# StationModule.net
KiCad netlist of a schematic drawn in EAGLE
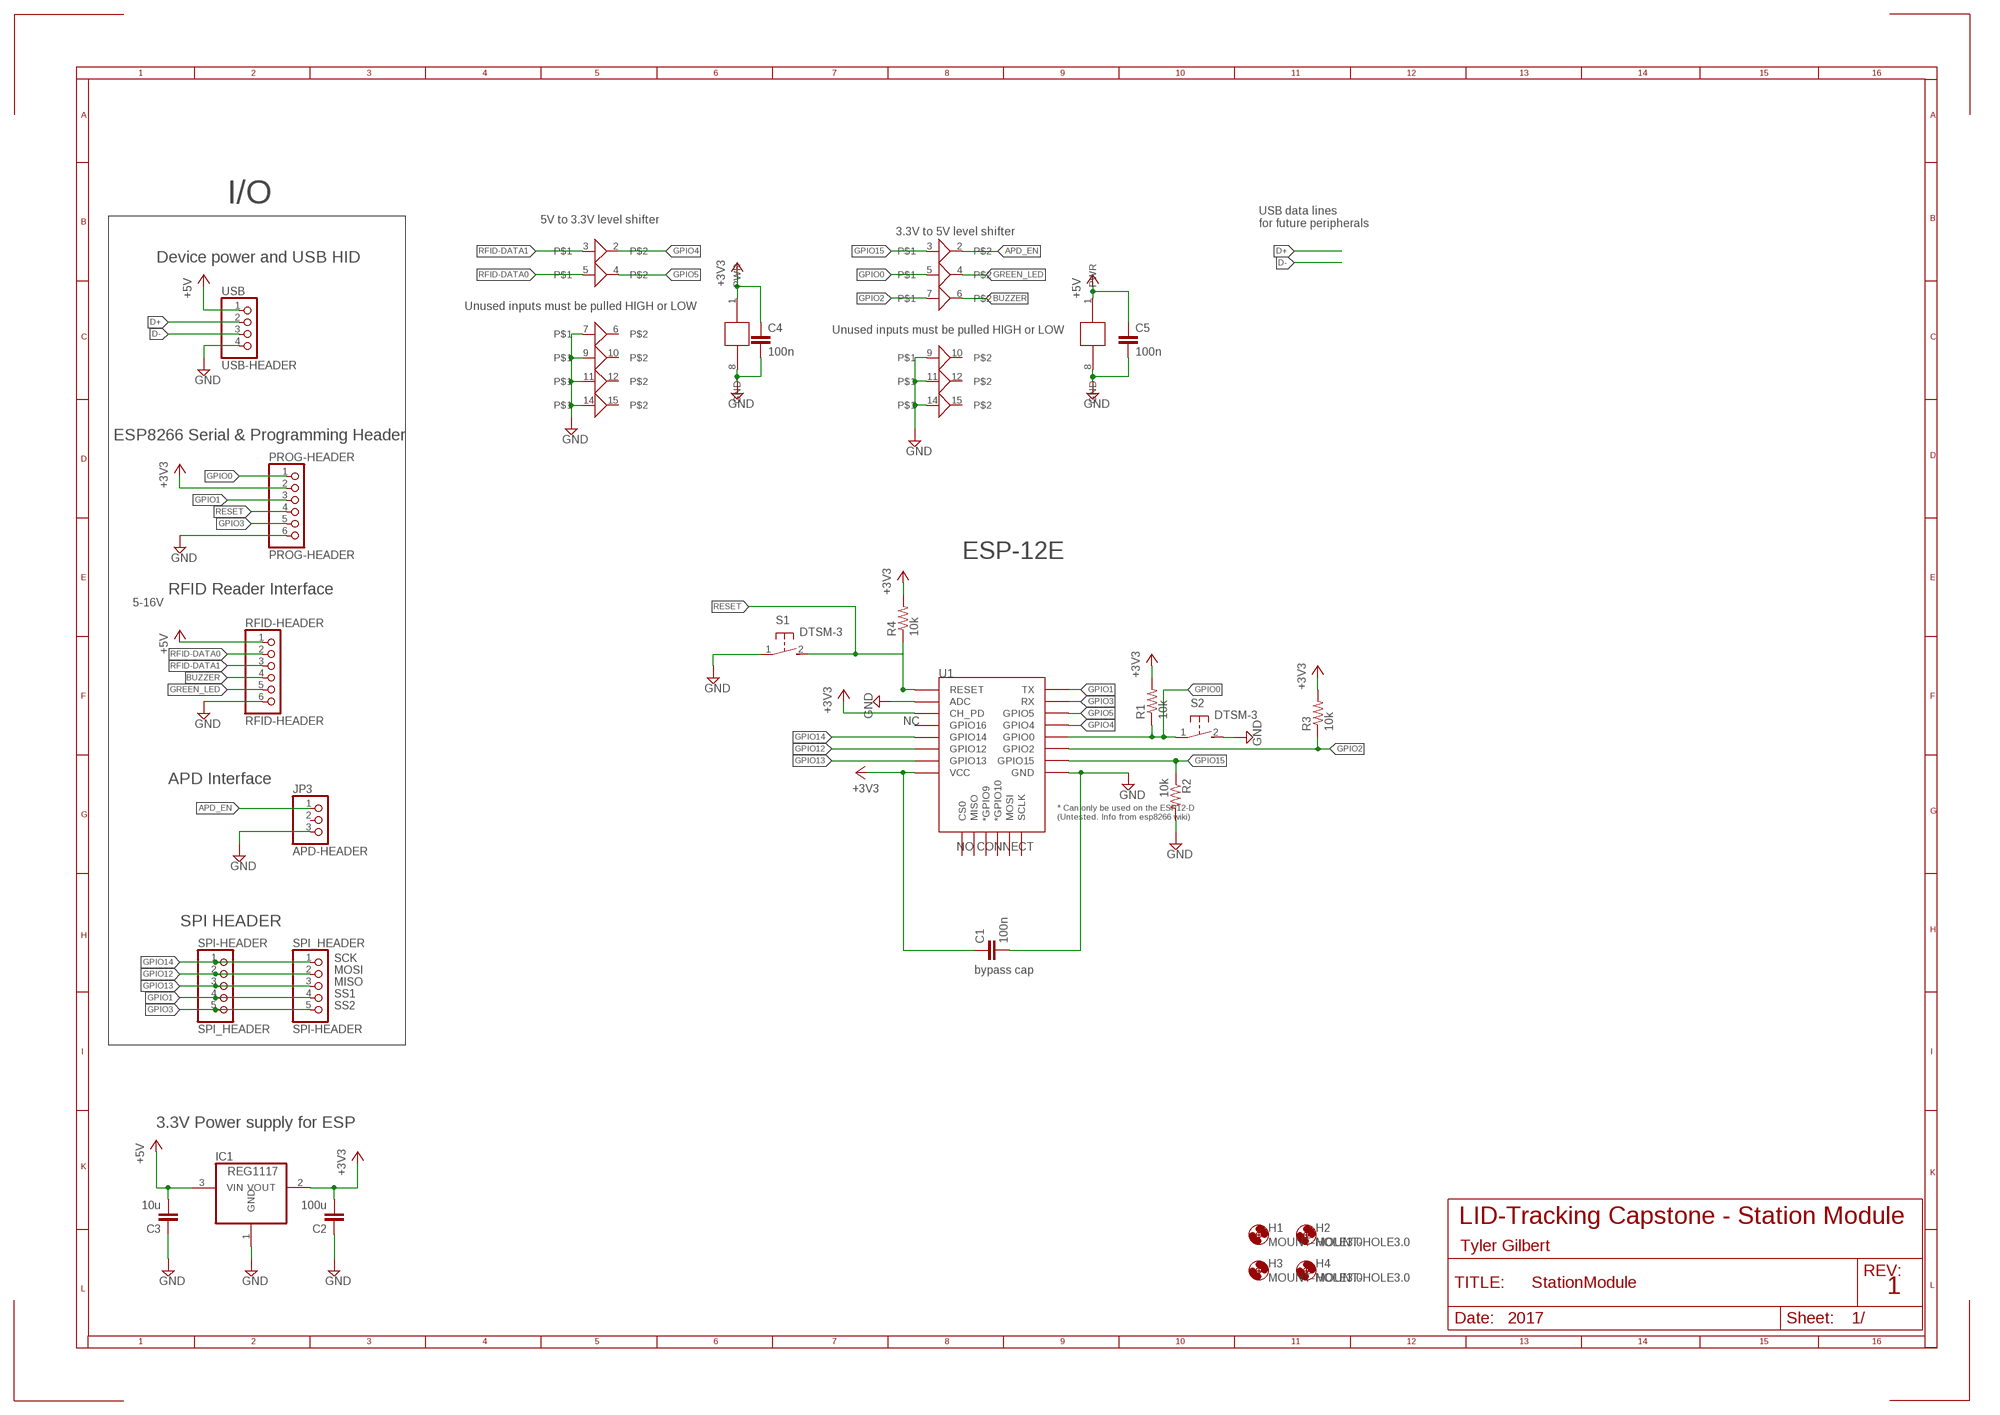
[diagram p0: schematic, sheet 1]

(export (version "E")
  (design (tool "Eeschema 10.0.6"))
  (components
    (comp (ref "C1")
      (value "100n")
      (footprint "eagle-import:C0805K")
      (libsource (lib "eagle-import") (part "C-EUC0805K"))
    )
    (comp (ref "C2")
      (value "100u")
      (footprint "eagle-import:C0805K")
      (libsource (lib "eagle-import") (part "C-EUC0805K"))
    )
    (comp (ref "C3")
      (value "10u")
      (footprint "eagle-import:C0805K")
      (libsource (lib "eagle-import") (part "C-EUC0805K"))
    )
    (comp (ref "C4")
      (value "100n")
      (footprint "eagle-import:C0805K")
      (libsource (lib "eagle-import") (part "C-EUC0805K"))
    )
    (comp (ref "C5")
      (value "100n")
      (footprint "eagle-import:C0805K")
      (libsource (lib "eagle-import") (part "C-EUC0805K"))
    )
    (comp (ref "H1")
      (value "MOUNT-HOLE3.0")
      (footprint "eagle-import:3,0")
      (libsource (lib "eagle-import") (part "MOUNT-HOLE3.0"))
    )
    (comp (ref "H2")
      (value "MOUNT-HOLE3.0")
      (footprint "eagle-import:3,0")
      (libsource (lib "eagle-import") (part "MOUNT-HOLE3.0"))
    )
    (comp (ref "H3")
      (value "MOUNT-HOLE3.0")
      (footprint "eagle-import:3,0")
      (libsource (lib "eagle-import") (part "MOUNT-HOLE3.0"))
    )
    (comp (ref "H4")
      (value "MOUNT-HOLE3.0")
      (footprint "eagle-import:3,0")
      (libsource (lib "eagle-import") (part "MOUNT-HOLE3.0"))
    )
    (comp (ref "IC1")
      (value "REG1117")
      (footprint "eagle-import:SOT223")
      (libsource (lib "eagle-import") (part "REG1117"))
    )
    (comp (ref "JP3")
      (value "APD-HEADER")
      (footprint "eagle-import:1X03")
      (libsource (lib "eagle-import") (part "PINHD-1X3"))
    )
    (comp (ref "PROG-HEADER")
      (value "PROG-HEADER")
      (footprint "eagle-import:1X06")
      (libsource (lib "eagle-import") (part "PINHD-1X6"))
    )
    (comp (ref "R1")
      (value "10k")
      (footprint "eagle-import:R0805")
      (libsource (lib "eagle-import") (part "R-US_R0805"))
    )
    (comp (ref "R2")
      (value "10k")
      (footprint "eagle-import:R0805")
      (libsource (lib "eagle-import") (part "R-US_R0805"))
    )
    (comp (ref "R3")
      (value "10k")
      (footprint "eagle-import:R0805")
      (libsource (lib "eagle-import") (part "R-US_R0805"))
    )
    (comp (ref "R4")
      (value "10k")
      (footprint "eagle-import:R0805")
      (libsource (lib "eagle-import") (part "R-US_R0805"))
    )
    (comp (ref "RFID-HEADER")
      (value "RFID-HEADER")
      (footprint "eagle-import:1X06")
      (libsource (lib "eagle-import") (part "PINHD-1X6"))
    )
    (comp (ref "S1")
      (value "DTSM-3")
      (footprint "eagle-import:DTSM-3")
      (libsource (lib "eagle-import") (part "DTSM-3"))
    )
    (comp (ref "S2")
      (value "DTSM-3")
      (footprint "eagle-import:DTSM-3")
      (libsource (lib "eagle-import") (part "DTSM-3"))
    )
    (comp (ref "SPI-HEADER")
      (value "SPI_HEADER")
      (footprint "eagle-import:1X05")
      (libsource (lib "eagle-import") (part "PINHD-1X5"))
    )
    (comp (ref "SPI_HEADER")
      (value "SPI-HEADER")
      (footprint "eagle-import:1X05")
      (libsource (lib "eagle-import") (part "PINHD-1X5"))
    )
    (comp (ref "U$1")
      (value "4050B")
      (footprint "eagle-import:SOIC16N")
      (libsource (lib "eagle-import") (part "4050B"))
    )
    (comp (ref "U$2")
      (value "4050B")
      (footprint "eagle-import:SOIC16N")
      (libsource (lib "eagle-import") (part "4050B"))
    )
    (comp (ref "U1")
      (value "ESP12ESMD")
      (footprint "eagle-import:ESP12E-SMD")
      (libsource (lib "eagle-import") (part "ESP12ESMD"))
    )
    (comp (ref "USB")
      (value "USB-HEADER")
      (footprint "eagle-import:1X04")
      (libsource (lib "eagle-import") (part "PINHD-1X4"))
    )
  )
  (nets
    (net (code "1") (name "+3V3") (class "Default")
      (node (ref "C1") (pin "1") (pinfunction "1_1") (pintype "passive"))
      (node (ref "C2") (pin "2") (pinfunction "2_2") (pintype "passive"))
      (node (ref "C4") (pin "1") (pinfunction "1_1") (pintype "passive"))
      (node (ref "IC1") (pin "2") (pinfunction "VOUT_2") (pintype "output"))
      (node (ref "PROG-HEADER") (pin "2") (pinfunction "2_2") (pintype "passive"))
      (node (ref "R1") (pin "2") (pinfunction "2_2") (pintype "passive"))
      (node (ref "R3") (pin "2") (pinfunction "2_2") (pintype "passive"))
      (node (ref "R4") (pin "2") (pinfunction "2_2") (pintype "passive"))
      (node (ref "U$1") (pin "1") (pinfunction "PWR_1") (pintype "power_in"))
      (node (ref "U1") (pin "CH_PD") (pinfunction "CH_PD_CH_PD") (pintype "bidirectional"))
      (node (ref "U1") (pin "VCC") (pinfunction "VCC_VCC") (pintype "bidirectional"))
    )
    (net (code "2") (name "+5V") (class "Default")
      (node (ref "C3") (pin "2") (pinfunction "2_2") (pintype "passive"))
      (node (ref "C5") (pin "1") (pinfunction "1_1") (pintype "passive"))
      (node (ref "IC1") (pin "3") (pinfunction "VIN_3") (pintype "input"))
      (node (ref "RFID-HEADER") (pin "1") (pinfunction "1_1") (pintype "passive"))
      (node (ref "U$2") (pin "1") (pinfunction "PWR_1") (pintype "power_in"))
      (node (ref "USB") (pin "1") (pinfunction "1_1") (pintype "passive"))
    )
    (net (code "3") (name "APD_EN") (class "Default")
      (node (ref "JP3") (pin "1") (pinfunction "1_1") (pintype "passive"))
      (node (ref "U$2") (pin "2") (pinfunction "P$2_2") (pintype "bidirectional"))
    )
    (net (code "4") (name "BUZZER") (class "Default")
      (node (ref "RFID-HEADER") (pin "4") (pinfunction "4_4") (pintype "passive"))
      (node (ref "U$2") (pin "6") (pinfunction "P$2_6") (pintype "bidirectional"))
    )
    (net (code "5") (name "D+") (class "Default")
      (node (ref "USB") (pin "2") (pinfunction "2_2") (pintype "passive"))
    )
    (net (code "6") (name "D-") (class "Default")
      (node (ref "USB") (pin "3") (pinfunction "3_3") (pintype "passive"))
    )
    (net (code "7") (name "GND") (class "Default")
      (node (ref "C1") (pin "2") (pinfunction "2_2") (pintype "passive"))
      (node (ref "C2") (pin "1") (pinfunction "1_1") (pintype "passive"))
      (node (ref "C3") (pin "1") (pinfunction "1_1") (pintype "passive"))
      (node (ref "C4") (pin "2") (pinfunction "2_2") (pintype "passive"))
      (node (ref "C5") (pin "2") (pinfunction "2_2") (pintype "passive"))
      (node (ref "IC1") (pin "1") (pinfunction "GND_1") (pintype "power_in"))
      (node (ref "JP3") (pin "3") (pinfunction "3_3") (pintype "passive"))
      (node (ref "PROG-HEADER") (pin "6") (pinfunction "6_6") (pintype "passive"))
      (node (ref "R2") (pin "2") (pinfunction "2_2") (pintype "passive"))
      (node (ref "RFID-HEADER") (pin "6") (pinfunction "6_6") (pintype "passive"))
      (node (ref "S1") (pin "1") (pinfunction "1_1") (pintype "passive"))
      (node (ref "S2") (pin "2") (pinfunction "2_2") (pintype "passive"))
      (node (ref "U$1") (pin "11") (pinfunction "P$1_11") (pintype "bidirectional"))
      (node (ref "U$1") (pin "14") (pinfunction "P$1_14") (pintype "bidirectional"))
      (node (ref "U$1") (pin "7") (pinfunction "P$1_7") (pintype "bidirectional"))
      (node (ref "U$1") (pin "8") (pinfunction "GND_8") (pintype "power_in"))
      (node (ref "U$1") (pin "9") (pinfunction "P$1_9") (pintype "bidirectional"))
      (node (ref "U$2") (pin "11") (pinfunction "P$1_11") (pintype "bidirectional"))
      (node (ref "U$2") (pin "14") (pinfunction "P$1_14") (pintype "bidirectional"))
      (node (ref "U$2") (pin "8") (pinfunction "GND_8") (pintype "power_in"))
      (node (ref "U$2") (pin "9") (pinfunction "P$1_9") (pintype "bidirectional"))
      (node (ref "U1") (pin "ADC") (pinfunction "ADC_ADC") (pintype "bidirectional"))
      (node (ref "U1") (pin "GND") (pinfunction "GND_GND") (pintype "bidirectional"))
      (node (ref "USB") (pin "4") (pinfunction "4_4") (pintype "passive"))
    )
    (net (code "8") (name "GPIO0") (class "Default")
      (node (ref "PROG-HEADER") (pin "1") (pinfunction "1_1") (pintype "passive"))
      (node (ref "R1") (pin "1") (pinfunction "1_1") (pintype "passive"))
      (node (ref "S2") (pin "1") (pinfunction "1_1") (pintype "passive"))
      (node (ref "U$2") (pin "5") (pinfunction "P$1_5") (pintype "bidirectional"))
      (node (ref "U1") (pin "GPIO0") (pinfunction "GPIO0_GPIO0") (pintype "bidirectional"))
    )
    (net (code "9") (name "GPIO1") (class "Default")
      (node (ref "PROG-HEADER") (pin "3") (pinfunction "3_3") (pintype "passive"))
      (node (ref "SPI-HEADER") (pin "4") (pinfunction "4_4") (pintype "passive"))
      (node (ref "SPI_HEADER") (pin "4") (pinfunction "4_4") (pintype "passive"))
      (node (ref "U1") (pin "TXD0") (pinfunction "TX_TXD0") (pintype "bidirectional"))
    )
    (net (code "10") (name "GPIO2") (class "Default")
      (node (ref "R3") (pin "1") (pinfunction "1_1") (pintype "passive"))
      (node (ref "U$2") (pin "7") (pinfunction "P$1_7") (pintype "bidirectional"))
      (node (ref "U1") (pin "GPIO2") (pinfunction "GPIO2_GPIO2") (pintype "bidirectional"))
    )
    (net (code "11") (name "GPIO3") (class "Default")
      (node (ref "PROG-HEADER") (pin "5") (pinfunction "5_5") (pintype "passive"))
      (node (ref "SPI-HEADER") (pin "5") (pinfunction "5_5") (pintype "passive"))
      (node (ref "SPI_HEADER") (pin "5") (pinfunction "5_5") (pintype "passive"))
      (node (ref "U1") (pin "RXD0") (pinfunction "RX_RXD0") (pintype "bidirectional"))
    )
    (net (code "12") (name "GPIO4") (class "Default")
      (node (ref "U$1") (pin "2") (pinfunction "P$2_2") (pintype "bidirectional"))
      (node (ref "U1") (pin "GPIO4") (pinfunction "GPIO4_GPIO4") (pintype "bidirectional"))
    )
    (net (code "13") (name "GPIO5") (class "Default")
      (node (ref "U$1") (pin "4") (pinfunction "P$2_4") (pintype "bidirectional"))
      (node (ref "U1") (pin "GPIO5") (pinfunction "GPIO5_GPIO5") (pintype "bidirectional"))
    )
    (net (code "14") (name "GPIO12") (class "Default")
      (node (ref "SPI-HEADER") (pin "2") (pinfunction "2_2") (pintype "passive"))
      (node (ref "SPI_HEADER") (pin "2") (pinfunction "2_2") (pintype "passive"))
      (node (ref "U1") (pin "GPIO12") (pinfunction "GPIO12_GPIO12") (pintype "bidirectional"))
    )
    (net (code "15") (name "GPIO13") (class "Default")
      (node (ref "SPI-HEADER") (pin "3") (pinfunction "3_3") (pintype "passive"))
      (node (ref "SPI_HEADER") (pin "3") (pinfunction "3_3") (pintype "passive"))
      (node (ref "U1") (pin "GPIO13") (pinfunction "GPIO13_GPIO13") (pintype "bidirectional"))
    )
    (net (code "16") (name "GPIO14") (class "Default")
      (node (ref "SPI-HEADER") (pin "1") (pinfunction "1_1") (pintype "passive"))
      (node (ref "SPI_HEADER") (pin "1") (pinfunction "1_1") (pintype "passive"))
      (node (ref "U1") (pin "GPIO14") (pinfunction "GPIO14_GPIO14") (pintype "bidirectional"))
    )
    (net (code "17") (name "GPIO15") (class "Default")
      (node (ref "R2") (pin "1") (pinfunction "1_1") (pintype "passive"))
      (node (ref "U$2") (pin "3") (pinfunction "P$1_3") (pintype "bidirectional"))
      (node (ref "U1") (pin "GPIO15") (pinfunction "GPIO15_GPIO15") (pintype "bidirectional"))
    )
    (net (code "18") (name "GREEN_LED") (class "Default")
      (node (ref "RFID-HEADER") (pin "5") (pinfunction "5_5") (pintype "passive"))
      (node (ref "U$2") (pin "4") (pinfunction "P$2_4") (pintype "bidirectional"))
    )
    (net (code "19") (name "RESET") (class "Default")
      (node (ref "PROG-HEADER") (pin "4") (pinfunction "4_4") (pintype "passive"))
      (node (ref "R4") (pin "1") (pinfunction "1_1") (pintype "passive"))
      (node (ref "S1") (pin "2") (pinfunction "2_2") (pintype "passive"))
      (node (ref "U1") (pin "RESET") (pinfunction "RESET_RESET") (pintype "bidirectional"))
    )
    (net (code "20") (name "RFID-DATA0") (class "Default")
      (node (ref "RFID-HEADER") (pin "2") (pinfunction "2_2") (pintype "passive"))
      (node (ref "U$1") (pin "5") (pinfunction "P$1_5") (pintype "bidirectional"))
    )
    (net (code "21") (name "RFID-DATA1") (class "Default")
      (node (ref "RFID-HEADER") (pin "3") (pinfunction "3_3") (pintype "passive"))
      (node (ref "U$1") (pin "3") (pinfunction "P$1_3") (pintype "bidirectional"))
    )
    (net (code "22") (name "unconnected-(JP3-Pad2)") (class "Default")
      (node (ref "JP3") (pin "2") (pinfunction "2_2") (pintype "passive"))
    )
    (net (code "23") (name "unconnected-(U$1C-P$2-Pad6)") (class "Default")
      (node (ref "U$1") (pin "6") (pinfunction "P$2_6") (pintype "bidirectional"))
    )
    (net (code "24") (name "unconnected-(U$1D-P$2-Pad10)") (class "Default")
      (node (ref "U$1") (pin "10") (pinfunction "P$2_10") (pintype "bidirectional"))
    )
    (net (code "25") (name "unconnected-(U$1E-P$2-Pad12)") (class "Default")
      (node (ref "U$1") (pin "12") (pinfunction "P$2_12") (pintype "bidirectional"))
    )
    (net (code "26") (name "unconnected-(U$1F-P$2-Pad15)") (class "Default")
      (node (ref "U$1") (pin "15") (pinfunction "P$2_15") (pintype "bidirectional"))
    )
    (net (code "27") (name "unconnected-(U$2D-P$2-Pad10)") (class "Default")
      (node (ref "U$2") (pin "10") (pinfunction "P$2_10") (pintype "bidirectional"))
    )
    (net (code "28") (name "unconnected-(U$2E-P$2-Pad12)") (class "Default")
      (node (ref "U$2") (pin "12") (pinfunction "P$2_12") (pintype "bidirectional"))
    )
    (net (code "29") (name "unconnected-(U$2F-P$2-Pad15)") (class "Default")
      (node (ref "U$2") (pin "15") (pinfunction "P$2_15") (pintype "bidirectional"))
    )
    (net (code "30") (name "unconnected-(U1-*GPIO9-PadGPIO9)") (class "Default")
      (node (ref "U1") (pin "GPIO9") (pinfunction "*GPIO9_GPIO9") (pintype "bidirectional"))
    )
    (net (code "31") (name "unconnected-(U1-*GPIO10-PadGPIO10)") (class "Default")
      (node (ref "U1") (pin "GPIO10") (pinfunction "*GPIO10_GPIO10") (pintype "bidirectional"))
    )
    (net (code "32") (name "unconnected-(U1-PadCS0)") (class "Default")
      (node (ref "U1") (pin "CS0") (pinfunction "CS0_CS0") (pintype "bidirectional"))
    )
    (net (code "33") (name "unconnected-(U1-PadGPIO16)") (class "Default")
      (node (ref "U1") (pin "GPIO16") (pinfunction "GPIO16_GPIO16") (pintype "bidirectional"))
    )
    (net (code "34") (name "unconnected-(U1-PadMISO)") (class "Default")
      (node (ref "U1") (pin "MISO") (pinfunction "MISO_MISO") (pintype "bidirectional"))
    )
    (net (code "35") (name "unconnected-(U1-PadMOSI)") (class "Default")
      (node (ref "U1") (pin "MOSI") (pinfunction "MOSI_MOSI") (pintype "bidirectional"))
    )
    (net (code "36") (name "unconnected-(U1-PadSCLK)") (class "Default")
      (node (ref "U1") (pin "SCLK") (pinfunction "SCLK_SCLK") (pintype "bidirectional"))
    )
  )
)
